# STM8S003.net
KiCad netlist of a schematic drawn in EAGLE
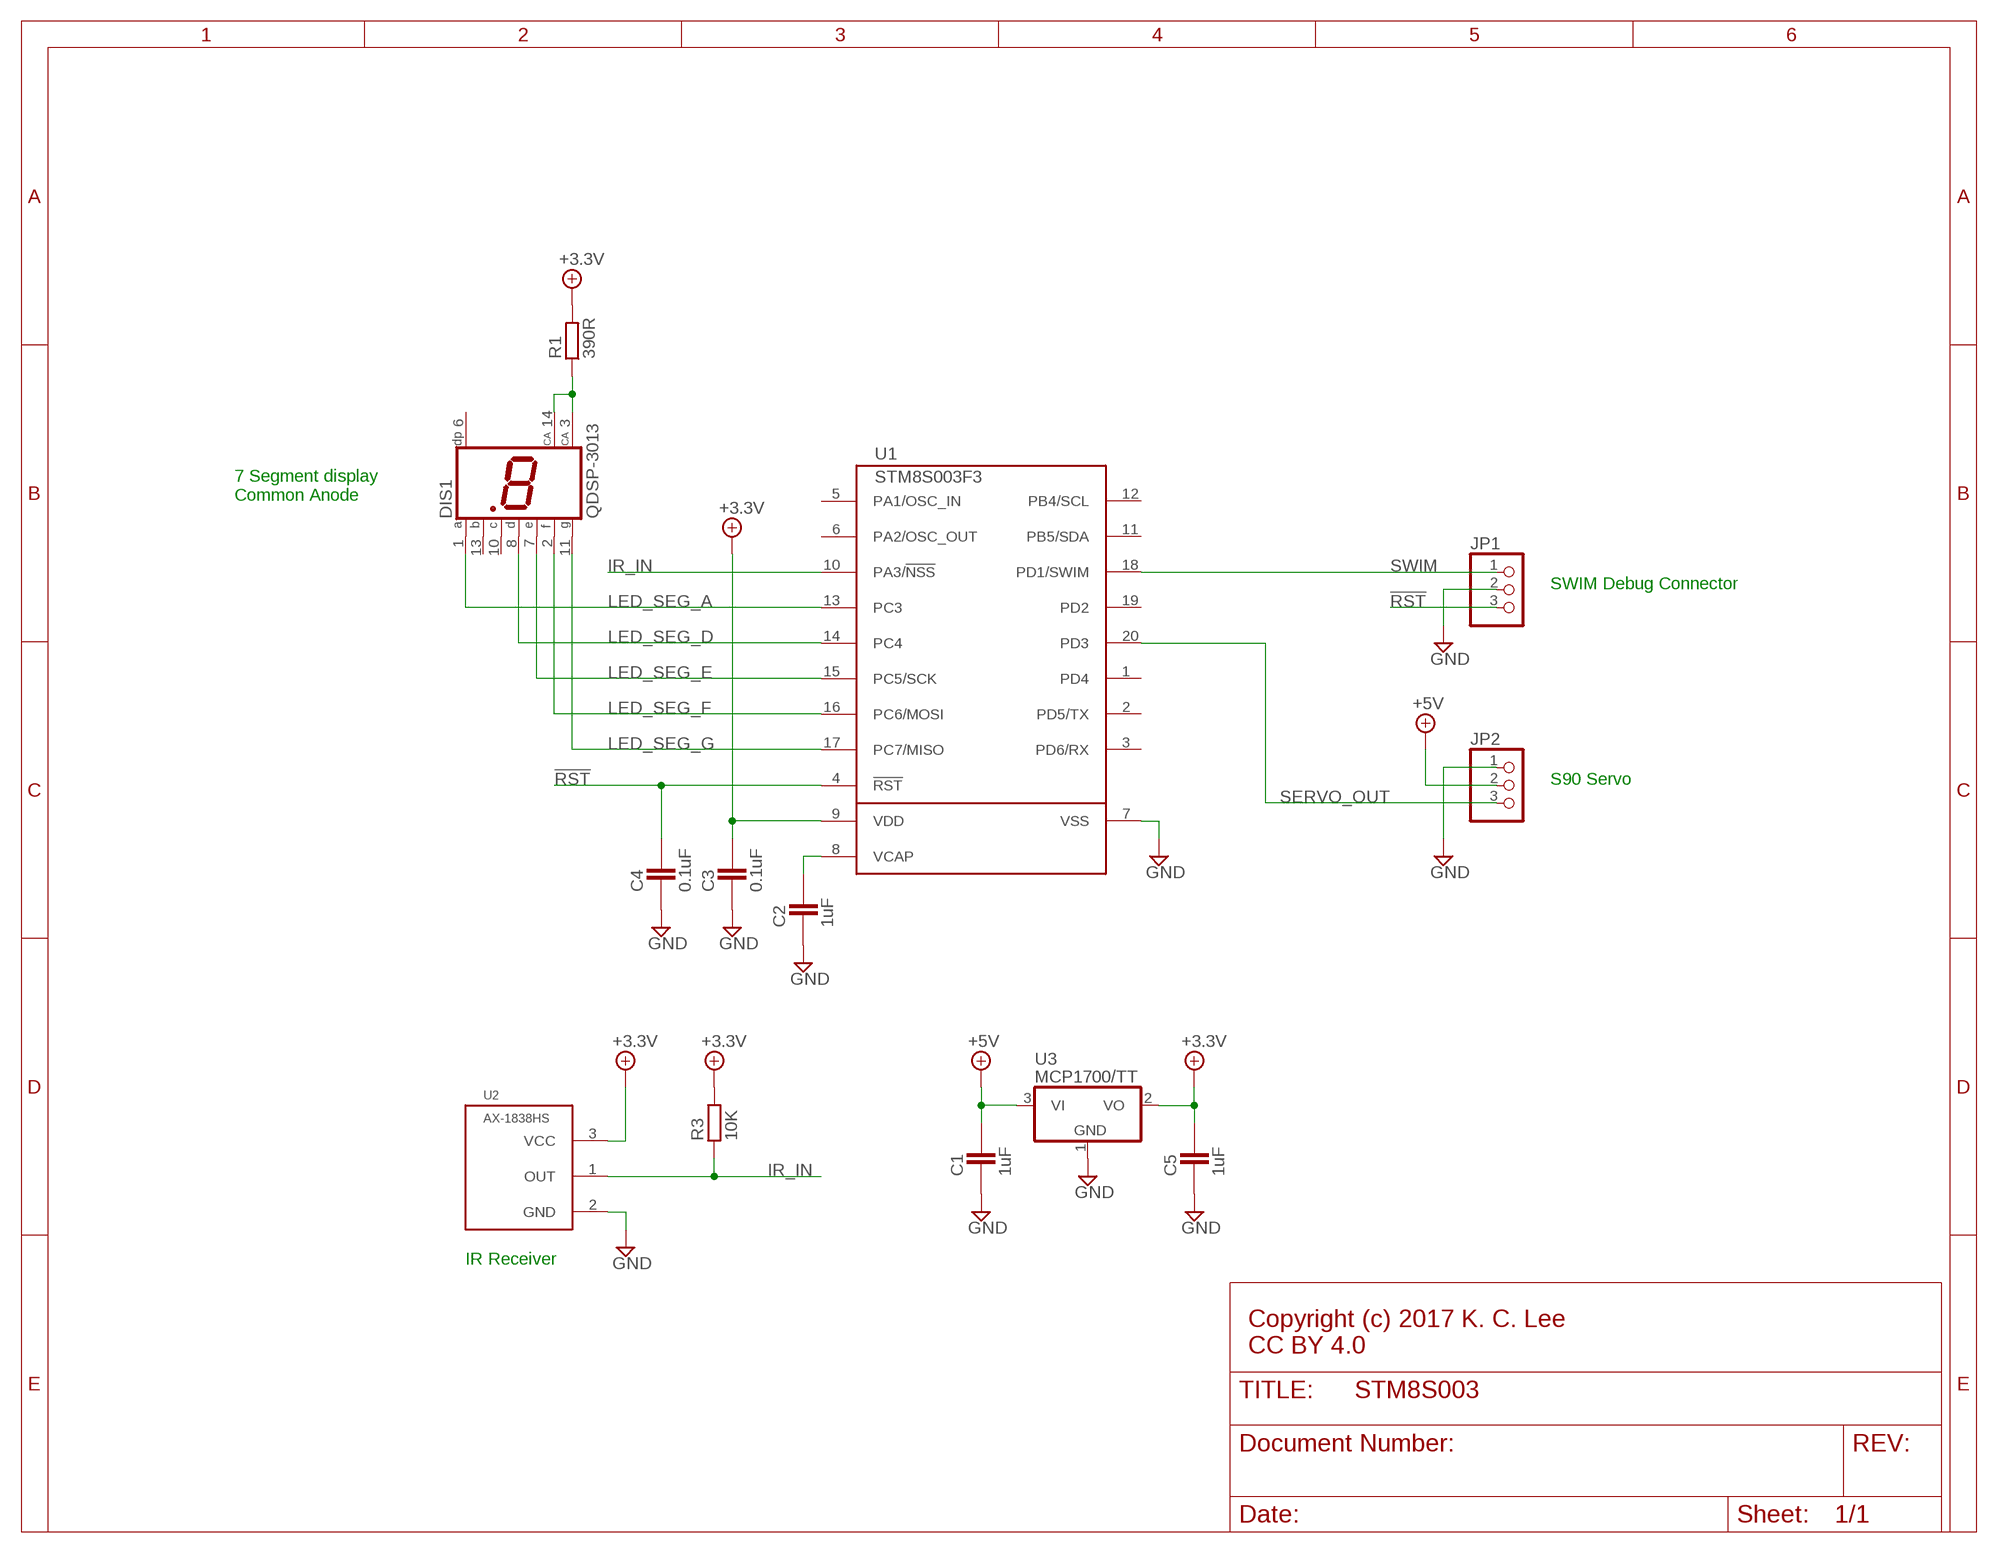
[diagram p0: schematic, sheet 1]

(export (version "E")
  (design (tool "Eeschema 10.0.6"))
  (components
    (comp (ref "C1")
      (value "1uF")
      (footprint "eagle-import:CAPC1608X92N")
      (libsource (lib "eagle-import") (part "CAPACITOR_0603"))
    )
    (comp (ref "C2")
      (value "1uF")
      (footprint "eagle-import:CAPC1608X92N")
      (libsource (lib "eagle-import") (part "CAPACITOR_0603"))
    )
    (comp (ref "C3")
      (value "0.1uF")
      (footprint "eagle-import:CAPC1608X92N")
      (libsource (lib "eagle-import") (part "CAPACITOR_0603"))
    )
    (comp (ref "C4")
      (value "0.1uF")
      (footprint "eagle-import:CAPC1608X92N")
      (libsource (lib "eagle-import") (part "CAPACITOR_0603"))
    )
    (comp (ref "C5")
      (value "1uF")
      (footprint "eagle-import:CAPC1608X92N")
      (libsource (lib "eagle-import") (part "CAPACITOR_0603"))
    )
    (comp (ref "DIS1")
      (value "QDSP-3013")
      (footprint "eagle-import:QDSP-3013")
      (libsource (lib "eagle-import") (part "QDSP-3013"))
    )
    (comp (ref "JP1")
      (value "PINHD-1X3")
      (footprint "eagle-import:1X03")
      (libsource (lib "eagle-import") (part "PINHD-1X3"))
    )
    (comp (ref "JP2")
      (value "PINHD-1X3")
      (footprint "eagle-import:1X03")
      (libsource (lib "eagle-import") (part "PINHD-1X3"))
    )
    (comp (ref "R1")
      (value "390R")
      (footprint "eagle-import:RESC1608X55N")
      (libsource (lib "eagle-import") (part "RESISTOR_0603"))
    )
    (comp (ref "R3")
      (value "10K")
      (footprint "eagle-import:RESC1608X55N")
      (libsource (lib "eagle-import") (part "RESISTOR_0603"))
    )
    (comp (ref "U1")
      (value "STM8S003F3")
      (footprint "eagle-import:TSSOP20")
      (libsource (lib "eagle-import") (part "STM8SX03F3"))
    )
    (comp (ref "U2")
      (value "AX-1838HS")
      (footprint "eagle-import:AX1838")
      (libsource (lib "eagle-import") (part "AX-1838HS"))
    )
    (comp (ref "U3")
      (value "MCP1700/TT")
      (footprint "eagle-import:SOT95P280X135-3N")
      (libsource (lib "eagle-import") (part "MCP1700/TT"))
    )
  )
  (nets
    (net (code "1") (name "+3.3V") (class "Default")
      (node (ref "C3") (pin "2") (pinfunction "2_2") (pintype "passive"))
      (node (ref "C5") (pin "2") (pinfunction "2_2") (pintype "passive"))
      (node (ref "R1") (pin "2") (pinfunction "2_2") (pintype "passive"))
      (node (ref "R3") (pin "2") (pinfunction "2_2") (pintype "passive"))
      (node (ref "U1") (pin "9") (pinfunction "VDD_9") (pintype "input"))
      (node (ref "U2") (pin "3") (pinfunction "VCC_3") (pintype "bidirectional"))
      (node (ref "U3") (pin "2") (pinfunction "VO_2") (pintype "passive"))
    )
    (net (code "2") (name "+5V") (class "Default")
      (node (ref "C1") (pin "2") (pinfunction "2_2") (pintype "passive"))
      (node (ref "JP2") (pin "2") (pinfunction "2_2") (pintype "passive"))
      (node (ref "U3") (pin "3") (pinfunction "VI_3") (pintype "input"))
    )
    (net (code "3") (name "/IR_IN") (class "Default")
      (node (ref "R3") (pin "1") (pinfunction "1_1") (pintype "passive"))
      (node (ref "U1") (pin "10") (pinfunction "PA3/~{NSS}_10") (pintype "bidirectional"))
      (node (ref "U2") (pin "1") (pinfunction "OUT_1") (pintype "bidirectional"))
    )
    (net (code "4") (name "/LED_SEG_A") (class "Default")
      (node (ref "DIS1") (pin "1") (pinfunction "A_1") (pintype "passive"))
      (node (ref "U1") (pin "13") (pinfunction "PC3_13") (pintype "bidirectional"))
    )
    (net (code "5") (name "/LED_SEG_D") (class "Default")
      (node (ref "DIS1") (pin "8") (pinfunction "D_8") (pintype "passive"))
      (node (ref "U1") (pin "14") (pinfunction "PC4_14") (pintype "bidirectional"))
    )
    (net (code "6") (name "/LED_SEG_E") (class "Default")
      (node (ref "DIS1") (pin "7") (pinfunction "E_7") (pintype "passive"))
      (node (ref "U1") (pin "15") (pinfunction "PC5/SCK_15") (pintype "bidirectional"))
    )
    (net (code "7") (name "/LED_SEG_F") (class "Default")
      (node (ref "DIS1") (pin "2") (pinfunction "F_2") (pintype "passive"))
      (node (ref "U1") (pin "16") (pinfunction "PC6/MOSI_16") (pintype "bidirectional"))
    )
    (net (code "8") (name "/LED_SEG_G") (class "Default")
      (node (ref "DIS1") (pin "11") (pinfunction "G_11") (pintype "passive"))
      (node (ref "U1") (pin "17") (pinfunction "PC7/MISO_17") (pintype "bidirectional"))
    )
    (net (code "9") (name "/SERVO_OUT") (class "Default")
      (node (ref "JP2") (pin "3") (pinfunction "3_3") (pintype "passive"))
      (node (ref "U1") (pin "20") (pinfunction "PD3_20") (pintype "bidirectional"))
    )
    (net (code "10") (name "/SWIM") (class "Default")
      (node (ref "JP1") (pin "1") (pinfunction "1_1") (pintype "passive"))
      (node (ref "U1") (pin "18") (pinfunction "PD1/SWIM_18") (pintype "input"))
    )
    (net (code "11") (name "/~{RST}") (class "Default")
      (node (ref "C4") (pin "2") (pinfunction "2_2") (pintype "passive"))
      (node (ref "JP1") (pin "3") (pinfunction "3_3") (pintype "passive"))
      (node (ref "U1") (pin "4") (pinfunction "~{RST}_4") (pintype "input"))
    )
    (net (code "12") (name "GND") (class "Default")
      (node (ref "C1") (pin "1") (pinfunction "1_1") (pintype "passive"))
      (node (ref "C2") (pin "1") (pinfunction "1_1") (pintype "passive"))
      (node (ref "C3") (pin "1") (pinfunction "1_1") (pintype "passive"))
      (node (ref "C4") (pin "1") (pinfunction "1_1") (pintype "passive"))
      (node (ref "C5") (pin "1") (pinfunction "1_1") (pintype "passive"))
      (node (ref "JP1") (pin "2") (pinfunction "2_2") (pintype "passive"))
      (node (ref "JP2") (pin "1") (pinfunction "1_1") (pintype "passive"))
      (node (ref "U1") (pin "7") (pinfunction "VSS_7") (pintype "input"))
      (node (ref "U2") (pin "2") (pinfunction "GND_2") (pintype "bidirectional"))
      (node (ref "U3") (pin "1") (pinfunction "GND_1") (pintype "passive"))
    )
    (net (code "13") (name "Net-(DIS1-CA-Pad14)") (class "Default")
      (node (ref "DIS1") (pin "14") (pinfunction "CA_14") (pintype "passive"))
      (node (ref "DIS1") (pin "3") (pinfunction "CA_3") (pintype "passive"))
      (node (ref "R1") (pin "1") (pinfunction "1_1") (pintype "passive"))
    )
    (net (code "14") (name "Net-(U1-VCAP)") (class "Default")
      (node (ref "C2") (pin "2") (pinfunction "2_2") (pintype "passive"))
      (node (ref "U1") (pin "8") (pinfunction "VCAP_8") (pintype "input"))
    )
    (net (code "15") (name "unconnected-(DIS1-B-Pad13)") (class "Default")
      (node (ref "DIS1") (pin "13") (pinfunction "B_13") (pintype "passive"))
    )
    (net (code "16") (name "unconnected-(DIS1-C-Pad10)") (class "Default")
      (node (ref "DIS1") (pin "10") (pinfunction "C_10") (pintype "passive"))
    )
    (net (code "17") (name "unconnected-(DIS1-DP-Pad6)") (class "Default")
      (node (ref "DIS1") (pin "6") (pinfunction "DP_6") (pintype "passive"))
    )
    (net (code "18") (name "unconnected-(U1-PA1{slash}OSC_IN-Pad5)") (class "Default")
      (node (ref "U1") (pin "5") (pinfunction "PA1/OSC_IN_5") (pintype "input"))
    )
    (net (code "19") (name "unconnected-(U1-PA2{slash}OSC_OUT-Pad6)") (class "Default")
      (node (ref "U1") (pin "6") (pinfunction "PA2/OSC_OUT_6") (pintype "output"))
    )
    (net (code "20") (name "unconnected-(U1-PB4{slash}SCL-Pad12)") (class "Default")
      (node (ref "U1") (pin "12") (pinfunction "PB4/SCL_12") (pintype "bidirectional"))
    )
    (net (code "21") (name "unconnected-(U1-PB5{slash}SDA-Pad11)") (class "Default")
      (node (ref "U1") (pin "11") (pinfunction "PB5/SDA_11") (pintype "bidirectional"))
    )
    (net (code "22") (name "unconnected-(U1-PD2-Pad19)") (class "Default")
      (node (ref "U1") (pin "19") (pinfunction "PD2_19") (pintype "bidirectional"))
    )
    (net (code "23") (name "unconnected-(U1-PD4-Pad1)") (class "Default")
      (node (ref "U1") (pin "1") (pinfunction "PD4_1") (pintype "bidirectional"))
    )
    (net (code "24") (name "unconnected-(U1-PD5{slash}TX-Pad2)") (class "Default")
      (node (ref "U1") (pin "2") (pinfunction "PD5/TX_2") (pintype "bidirectional"))
    )
    (net (code "25") (name "unconnected-(U1-PD6{slash}RX-Pad3)") (class "Default")
      (node (ref "U1") (pin "3") (pinfunction "PD6/RX_3") (pintype "bidirectional"))
    )
  )
)
